# mainPower.net
KiCad netlist of a schematic drawn in Altium Designer
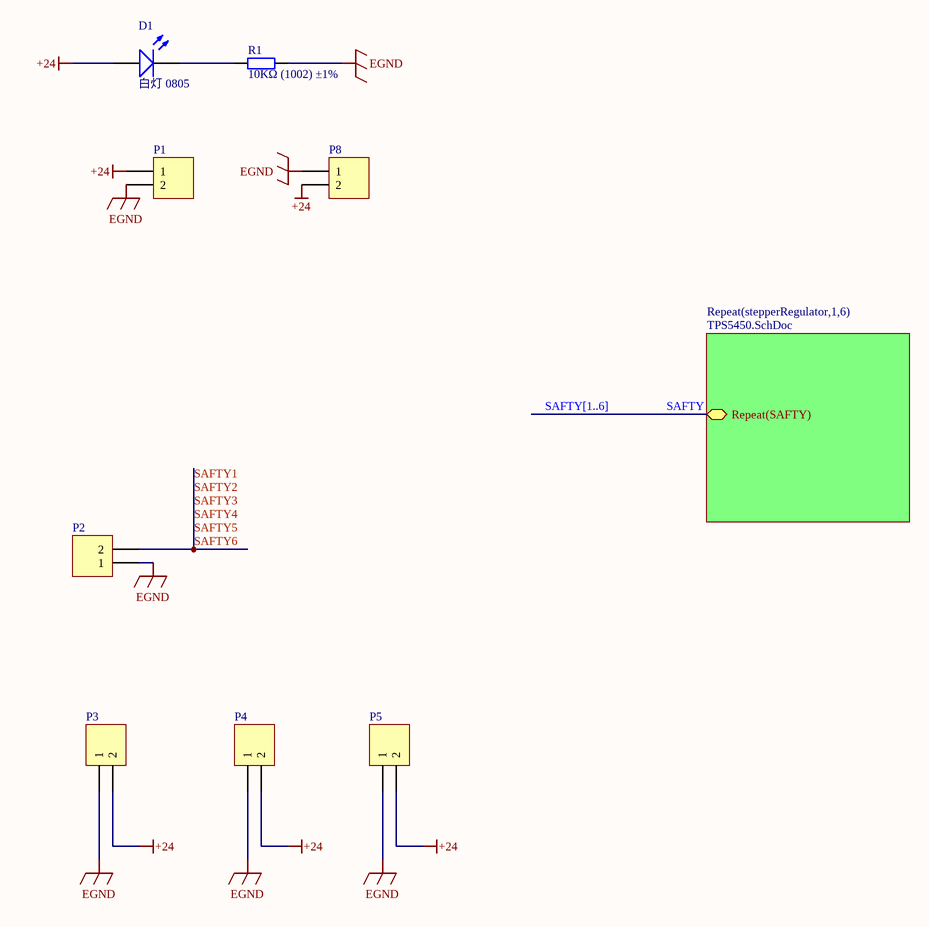
[diagram p0: mainPower.SchDoc]

(export (version "E")
  (design (tool "Eeschema 10.0.6"))
  (components
    (comp (ref "D1")
      (value "白灯 0805")
      (footprint "0805_LED_S1")
      (description "发光二极管")
      (libsource (lib "LED") (part "0805 白灯"))
    )
    (comp (ref "P1")
      (value "Header 2")
      (footprint "5.08-2P")
      (description "Header, 2-Pin")
      (fields (field (name "PUBLISHER") "Altium Limited"))
      (libsource (lib "") (part "Header 2_1"))
    )
    (comp (ref "P2")
      (value "Header 2")
      (footprint "5.08-2P")
      (description "Header, 2-Pin")
      (fields (field (name "PUBLISHER") "Altium Limited"))
      (libsource (lib "") (part "Header 2_2"))
    )
    (comp (ref "P3")
      (value "Header 2")
      (footprint "XH-2A")
      (description "Header, 2-Pin")
      (fields (field (name "PUBLISHER") "Altium Limited"))
      (libsource (lib "Sparks") (part "Header 2"))
    )
    (comp (ref "P4")
      (value "Header 2")
      (footprint "XH-2A")
      (description "Header, 2-Pin")
      (fields (field (name "PUBLISHER") "Altium Limited"))
      (libsource (lib "Sparks") (part "Header 2"))
    )
    (comp (ref "P5")
      (value "Header 2")
      (footprint "XH-2A")
      (description "Header, 2-Pin")
      (fields (field (name "PUBLISHER") "Altium Limited"))
      (libsource (lib "Sparks") (part "Header 2"))
    )
    (comp (ref "P8")
      (value "Header 2")
      (footprint "5.08-2P")
      (description "Header, 2-Pin")
      (fields (field (name "PUBLISHER") "Altium Limited"))
      (libsource (lib "") (part "Header 2_1"))
    )
    (comp (ref "R1")
      (value "10KΩ (1002) ±1%")
      (footprint "0805_R")
      (description "贴片电阻")
      (libsource (lib "Miscellaneous Devices LC") (part "0805 10KΩ (1002) 1%"))
    )
  )
  (nets
    (net (code "1") (name "+24") (class "Default")
      (node (ref "D1") (pin "A") (pinfunction "A_A") (pintype "passive"))
      (node (ref "P1") (pin "1") (pinfunction "1_1") (pintype "passive"))
      (node (ref "P3") (pin "2") (pinfunction "2_2") (pintype "passive"))
      (node (ref "P4") (pin "2") (pinfunction "2_2") (pintype "passive"))
      (node (ref "P5") (pin "2") (pinfunction "2_2") (pintype "passive"))
      (node (ref "P8") (pin "2") (pinfunction "2_2") (pintype "passive"))
    )
    (net (code "3") (name "/SAFTY6") (class "Default")
      (node (ref "P2") (pin "2") (pinfunction "2_2") (pintype "passive"))
    )
    (net (code "5") (name "EGND") (class "Default")
      (node (ref "P1") (pin "2") (pinfunction "2_2") (pintype "passive"))
      (node (ref "P2") (pin "1") (pinfunction "1_1") (pintype "passive"))
      (node (ref "P3") (pin "1") (pinfunction "1_1") (pintype "passive"))
      (node (ref "P4") (pin "1") (pinfunction "1_1") (pintype "passive"))
      (node (ref "P5") (pin "1") (pinfunction "1_1") (pintype "passive"))
      (node (ref "P8") (pin "1") (pinfunction "1_1") (pintype "passive"))
      (node (ref "R1") (pin "2") (pinfunction "2_2") (pintype "passive"))
    )
    (net (code "6") (name "Net-(D1-PadK)") (class "Default")
      (node (ref "D1") (pin "K") (pinfunction "K_K") (pintype "passive"))
      (node (ref "R1") (pin "1") (pinfunction "1_1") (pintype "passive"))
    )
  )
)
